# NCP1402-5V_Breakout.net
KiCad netlist of a schematic drawn in EAGLE
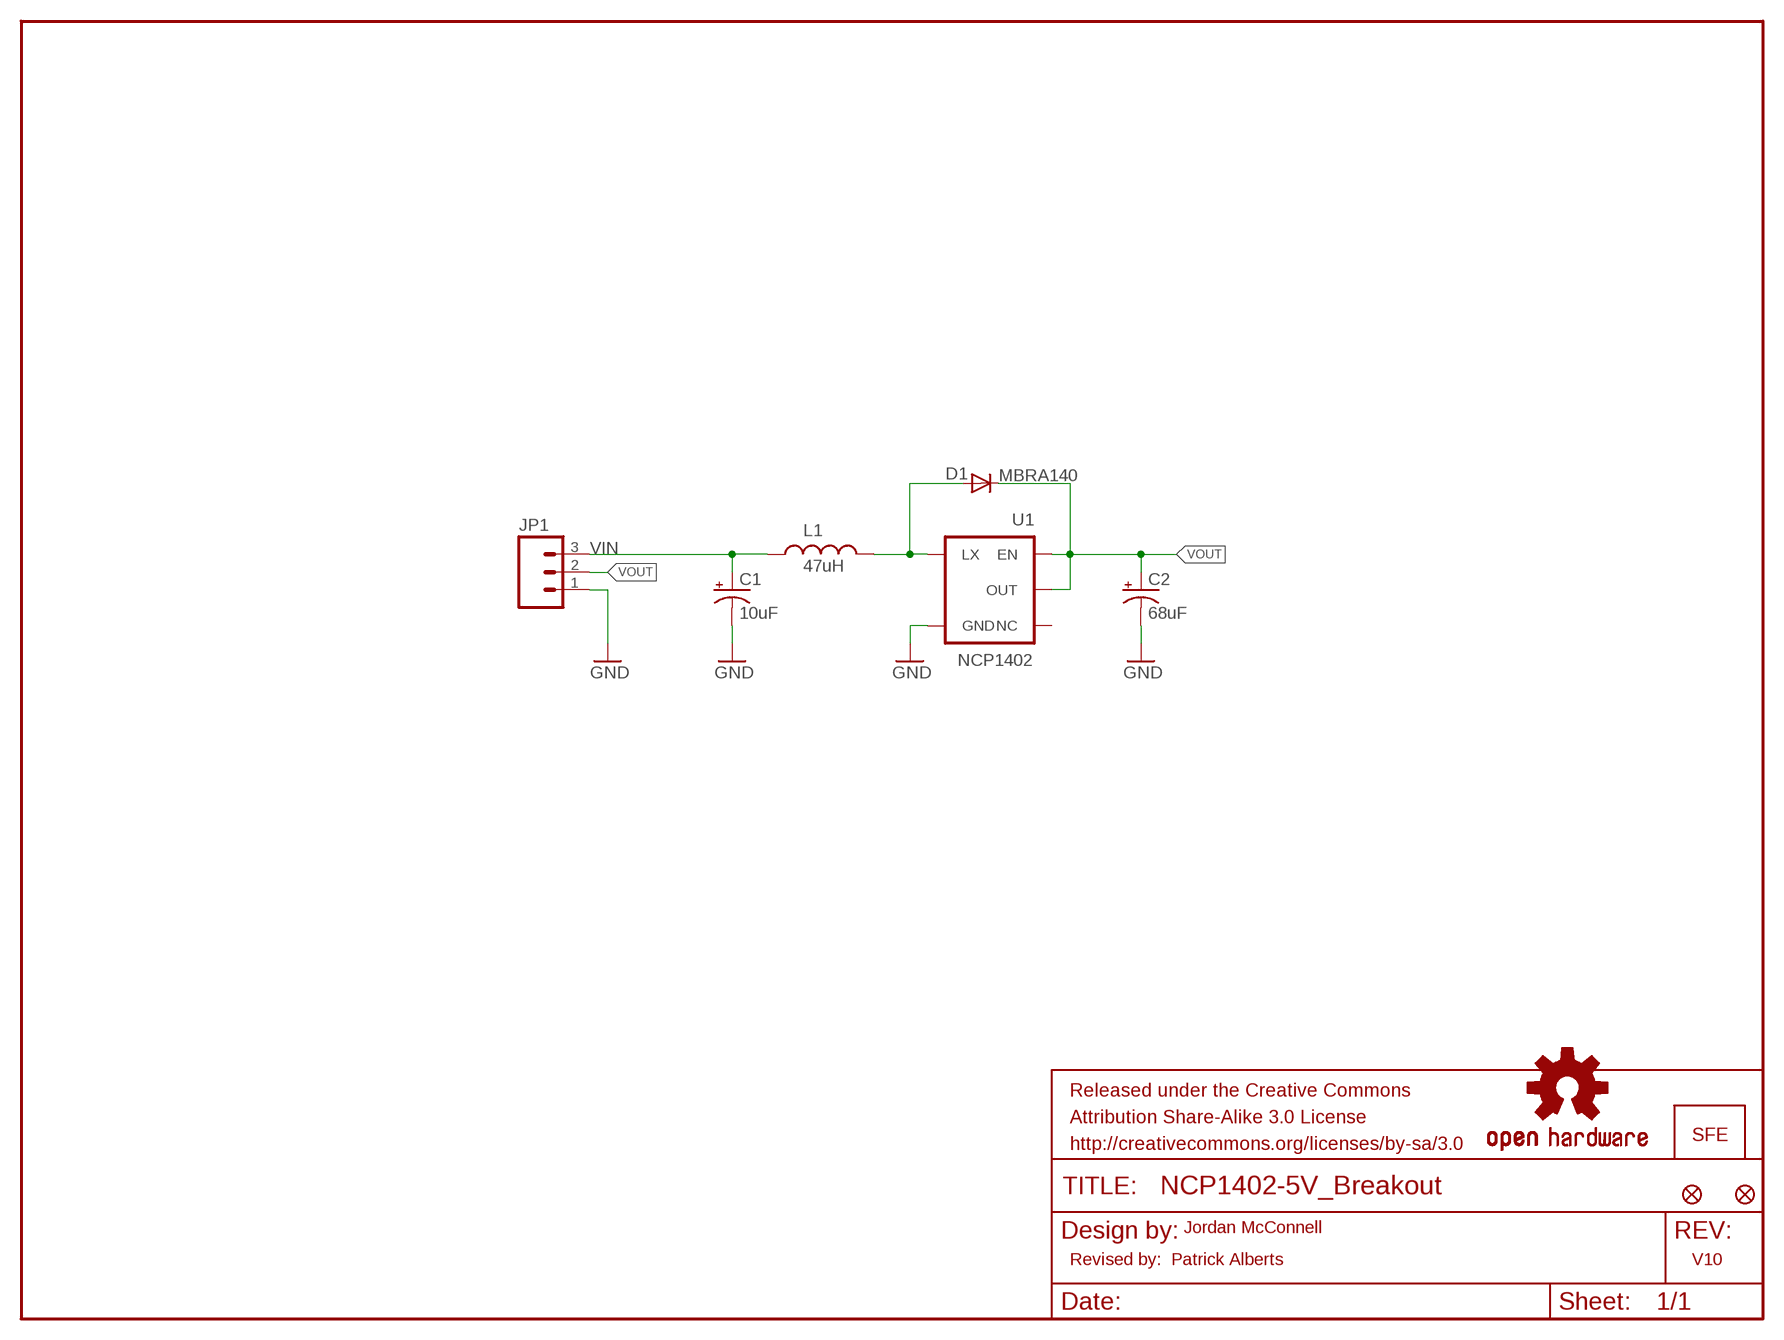
[diagram p0: schematic, sheet 1]

(export (version "E")
  (design (tool "Eeschema 10.0.6"))
  (components
    (comp (ref "C1")
      (value "10uF")
      (footprint "eagle-import:EIA3216")
      (libsource (lib "eagle-import") (part "CAP_POL1206"))
    )
    (comp (ref "C2")
      (value "68uF")
      (footprint "eagle-import:EIA3528")
      (libsource (lib "eagle-import") (part "CAP_POL3528"))
    )
    (comp (ref "D1")
      (value "MBRA140")
      (footprint "eagle-import:SMA-DIODE")
      (libsource (lib "eagle-import") (part "DIODESMA"))
    )
    (comp (ref "FID1")
      (value "FIDUCIAL1X2")
      (footprint "eagle-import:FIDUCIAL-1X2")
      (libsource (lib "eagle-import") (part "FIDUCIAL1X2"))
    )
    (comp (ref "FID2")
      (value "FIDUCIAL1X2")
      (footprint "eagle-import:FIDUCIAL-1X2")
      (libsource (lib "eagle-import") (part "FIDUCIAL1X2"))
    )
    (comp (ref "FRAME1")
      (value "FRAME-LETTER")
      (footprint "eagle-import:CREATIVE_COMMONS")
      (libsource (lib "eagle-import") (part "FRAME-LETTER"))
    )
    (comp (ref "JP1")
      (value "M03PTH")
      (footprint "eagle-import:1X03")
      (libsource (lib "eagle-import") (part "M03PTH"))
    )
    (comp (ref "JP2")
      (value "LOGO-SFESK")
      (footprint "eagle-import:SFE-LOGO-FLAME")
      (libsource (lib "eagle-import") (part "LOGO-SFESK"))
    )
    (comp (ref "L1")
      (value "47uH")
      (footprint "eagle-import:CR54")
      (libsource (lib "eagle-import") (part "INDUCTORCR54"))
    )
    (comp (ref "U$1")
      (value "OSHW-LOGOS")
      (footprint "eagle-import:OSHW-LOGO-S")
      (libsource (lib "eagle-import") (part "OSHW-LOGOS"))
    )
    (comp (ref "U1")
      (value "NCP1402")
      (footprint "eagle-import:SOT23-5")
      (libsource (lib "eagle-import") (part "V_REG_NCP1400SOT23-5"))
    )
  )
  (nets
    (net (code "1") (name "/VIN") (class "Default")
      (node (ref "C1") (pin "A") (pinfunction "+_A") (pintype "passive"))
      (node (ref "JP1") (pin "3") (pinfunction "3_3") (pintype "passive"))
      (node (ref "L1") (pin "P$1") (pinfunction "1_P$1") (pintype "passive"))
    )
    (net (code "2") (name "GND") (class "Default")
      (node (ref "C1") (pin "C") (pinfunction "-_C") (pintype "passive"))
      (node (ref "C2") (pin "C") (pinfunction "-_C") (pintype "passive"))
      (node (ref "JP1") (pin "1") (pinfunction "1_1") (pintype "passive"))
      (node (ref "U1") (pin "4") (pinfunction "GND_4") (pintype "input"))
    )
    (net (code "3") (name "Net-(L1-2)") (class "Default")
      (node (ref "D1") (pin "A") (pinfunction "A_A") (pintype "passive"))
      (node (ref "L1") (pin "P$2") (pinfunction "2_P$2") (pintype "passive"))
      (node (ref "U1") (pin "5") (pinfunction "LX_5") (pintype "input"))
    )
    (net (code "4") (name "VOUT") (class "Default")
      (node (ref "C2") (pin "A") (pinfunction "+_A") (pintype "passive"))
      (node (ref "D1") (pin "C") (pinfunction "C_C") (pintype "passive"))
      (node (ref "JP1") (pin "2") (pinfunction "2_2") (pintype "passive"))
      (node (ref "U1") (pin "1") (pinfunction "EN_1") (pintype "input"))
      (node (ref "U1") (pin "2") (pinfunction "OUT_2") (pintype "passive"))
    )
    (net (code "5") (name "unconnected-(U1-NC-Pad3)") (class "Default")
      (node (ref "U1") (pin "3") (pinfunction "NC_3") (pintype "input"))
    )
  )
)
